# test.net
KiCad netlist of a schematic drawn in EAGLE
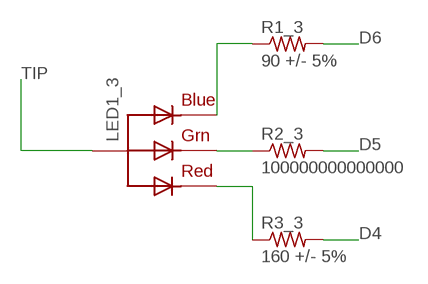
[diagram p0: schematic, sheet 1]

(export (version "E")
  (design (tool "Eeschema 10.0.6"))
  (components
    (comp (ref "LED1_3")
      (value "RGBLED_CA-5MM")
      (footprint "eagle-import:LED5MMRGB")
      (fields (field (name "CREATOR") "Swanson"))
      (libsource (lib "eagle-import") (part "RGBLED_CA-5MM"))
    )
    (comp (ref "R1_3")
      (value "90 +/- 5%")
      (footprint "eagle-import:RESC1608X55HS")
      (libsource (lib "eagle-import") (part "GENERIC-RESISTOR_1608-0603_CERAMIC"))
    )
    (comp (ref "R2_3")
      (value "100000000000000")
      (footprint "eagle-import:RESC1608X55HS")
      (libsource (lib "eagle-import") (part "GENERIC-RESISTOR_1608-0603_CERAMIC"))
    )
    (comp (ref "R3_3")
      (value "160 +/- 5%")
      (footprint "eagle-import:RESC1608X55HS")
      (libsource (lib "eagle-import") (part "GENERIC-RESISTOR_1608-0603_CERAMIC"))
    )
  )
  (nets
    (net (code "1") (name "/D4") (class "Default")
      (node (ref "R3_3") (pin "2") (pinfunction "2_2") (pintype "passive"))
    )
    (net (code "2") (name "/D5") (class "Default")
      (node (ref "R2_3") (pin "2") (pinfunction "2_2") (pintype "passive"))
    )
    (net (code "3") (name "/D6") (class "Default")
      (node (ref "R1_3") (pin "2") (pinfunction "2_2") (pintype "passive"))
    )
    (net (code "4") (name "/TIP") (class "Default")
      (node (ref "LED1_3") (pin "2") (pinfunction "VCC_2") (pintype "bidirectional"))
    )
    (net (code "5") (name "Net-(LED1_3-BLUE)") (class "Default")
      (node (ref "LED1_3") (pin "4") (pinfunction "BLUE_4") (pintype "bidirectional"))
      (node (ref "R1_3") (pin "1") (pinfunction "1_1") (pintype "passive"))
    )
    (net (code "6") (name "Net-(LED1_3-GREEN)") (class "Default")
      (node (ref "LED1_3") (pin "3") (pinfunction "GREEN_3") (pintype "bidirectional"))
      (node (ref "R2_3") (pin "1") (pinfunction "1_1") (pintype "passive"))
    )
    (net (code "7") (name "Net-(LED1_3-RED)") (class "Default")
      (node (ref "LED1_3") (pin "1") (pinfunction "RED_1") (pintype "bidirectional"))
      (node (ref "R3_3") (pin "1") (pinfunction "1_1") (pintype "passive"))
    )
  )
)
